# fdcanusb.net
KiCad netlist of a schematic drawn in EAGLE
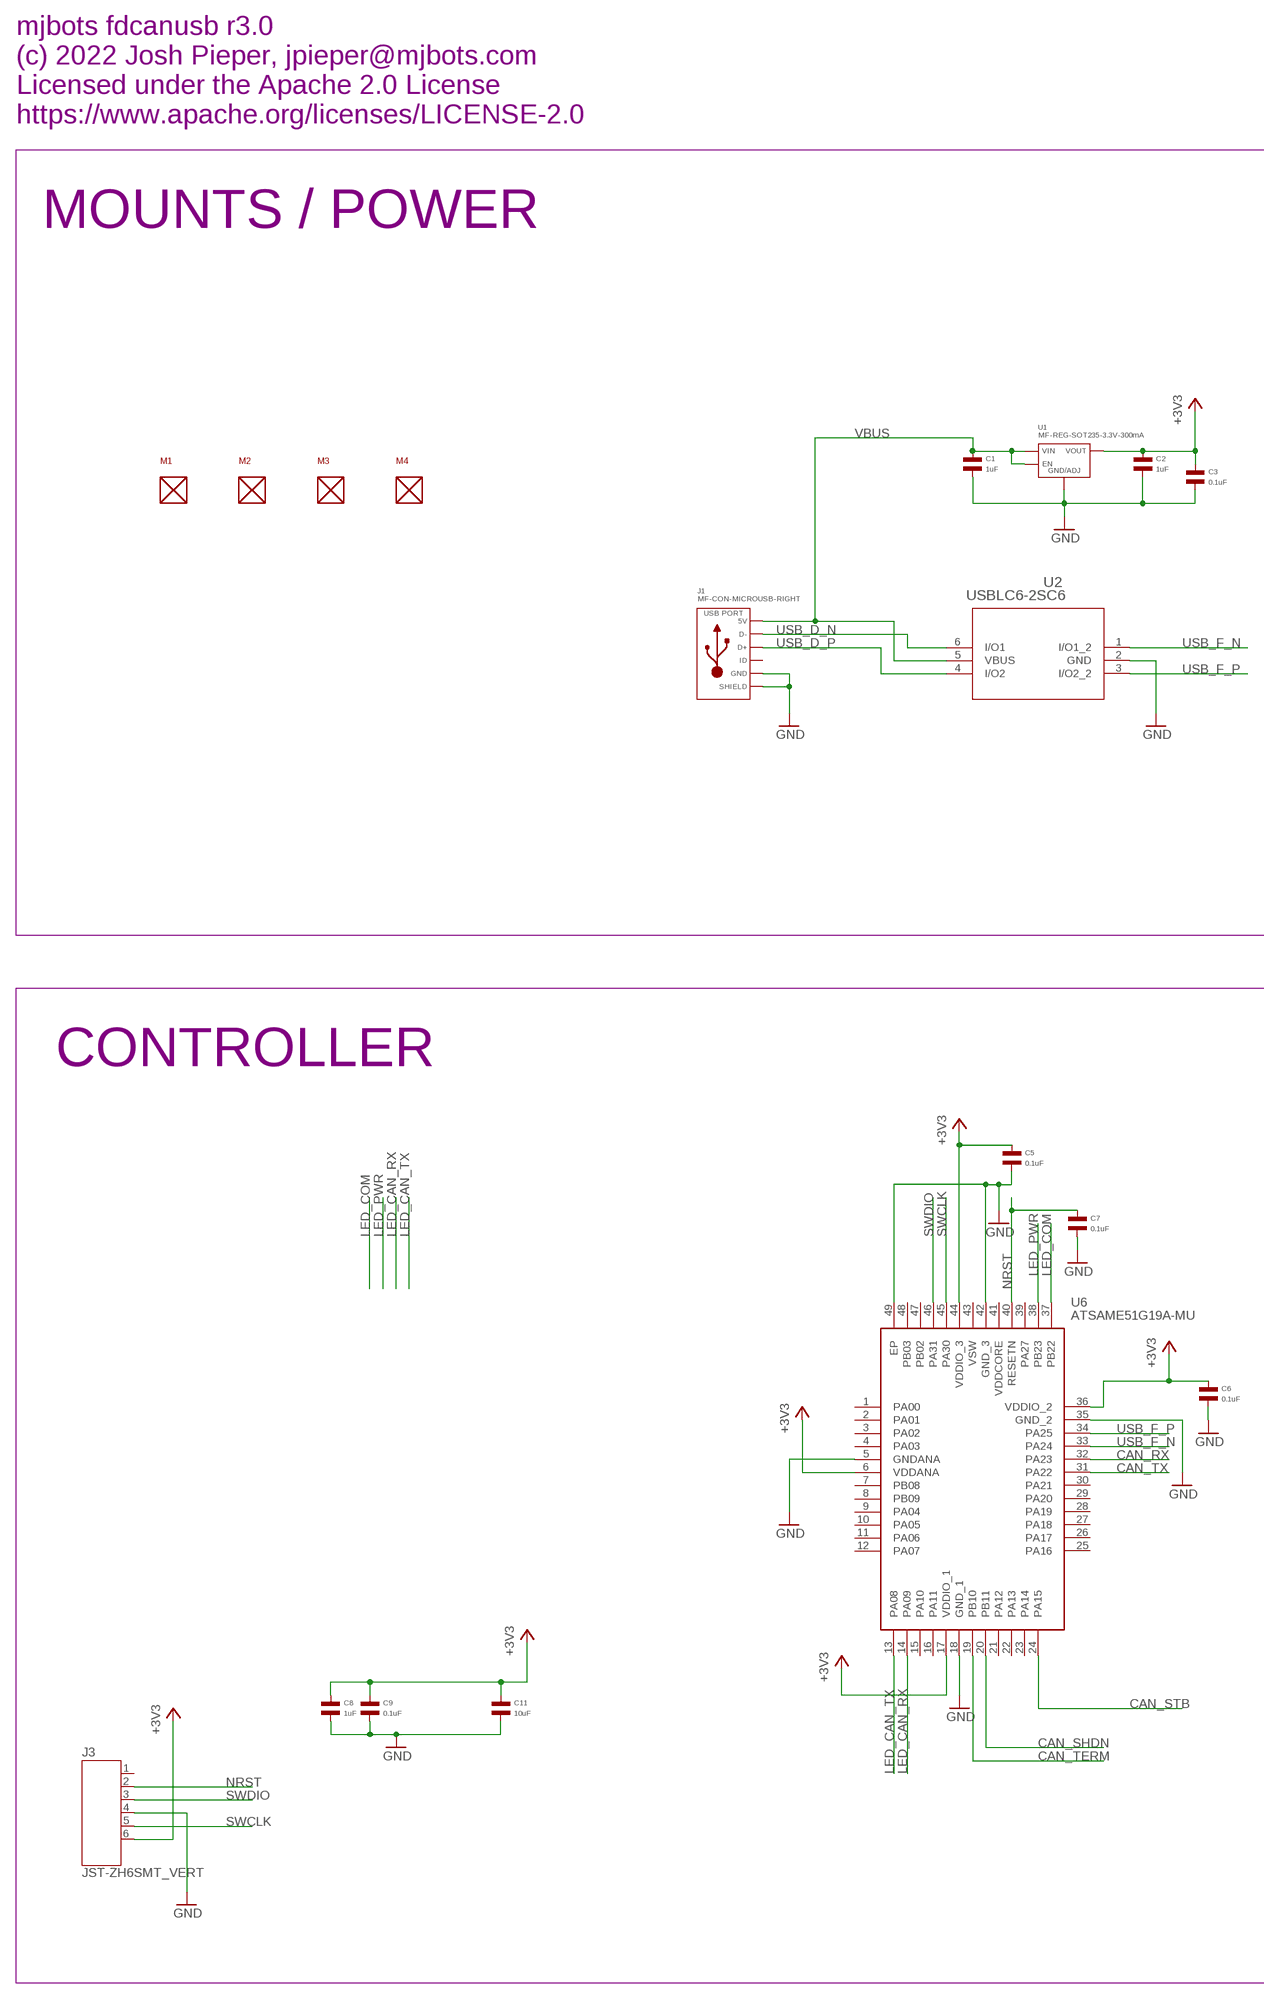
[diagram p0: schematic, sheet 1, part 1 of 2]
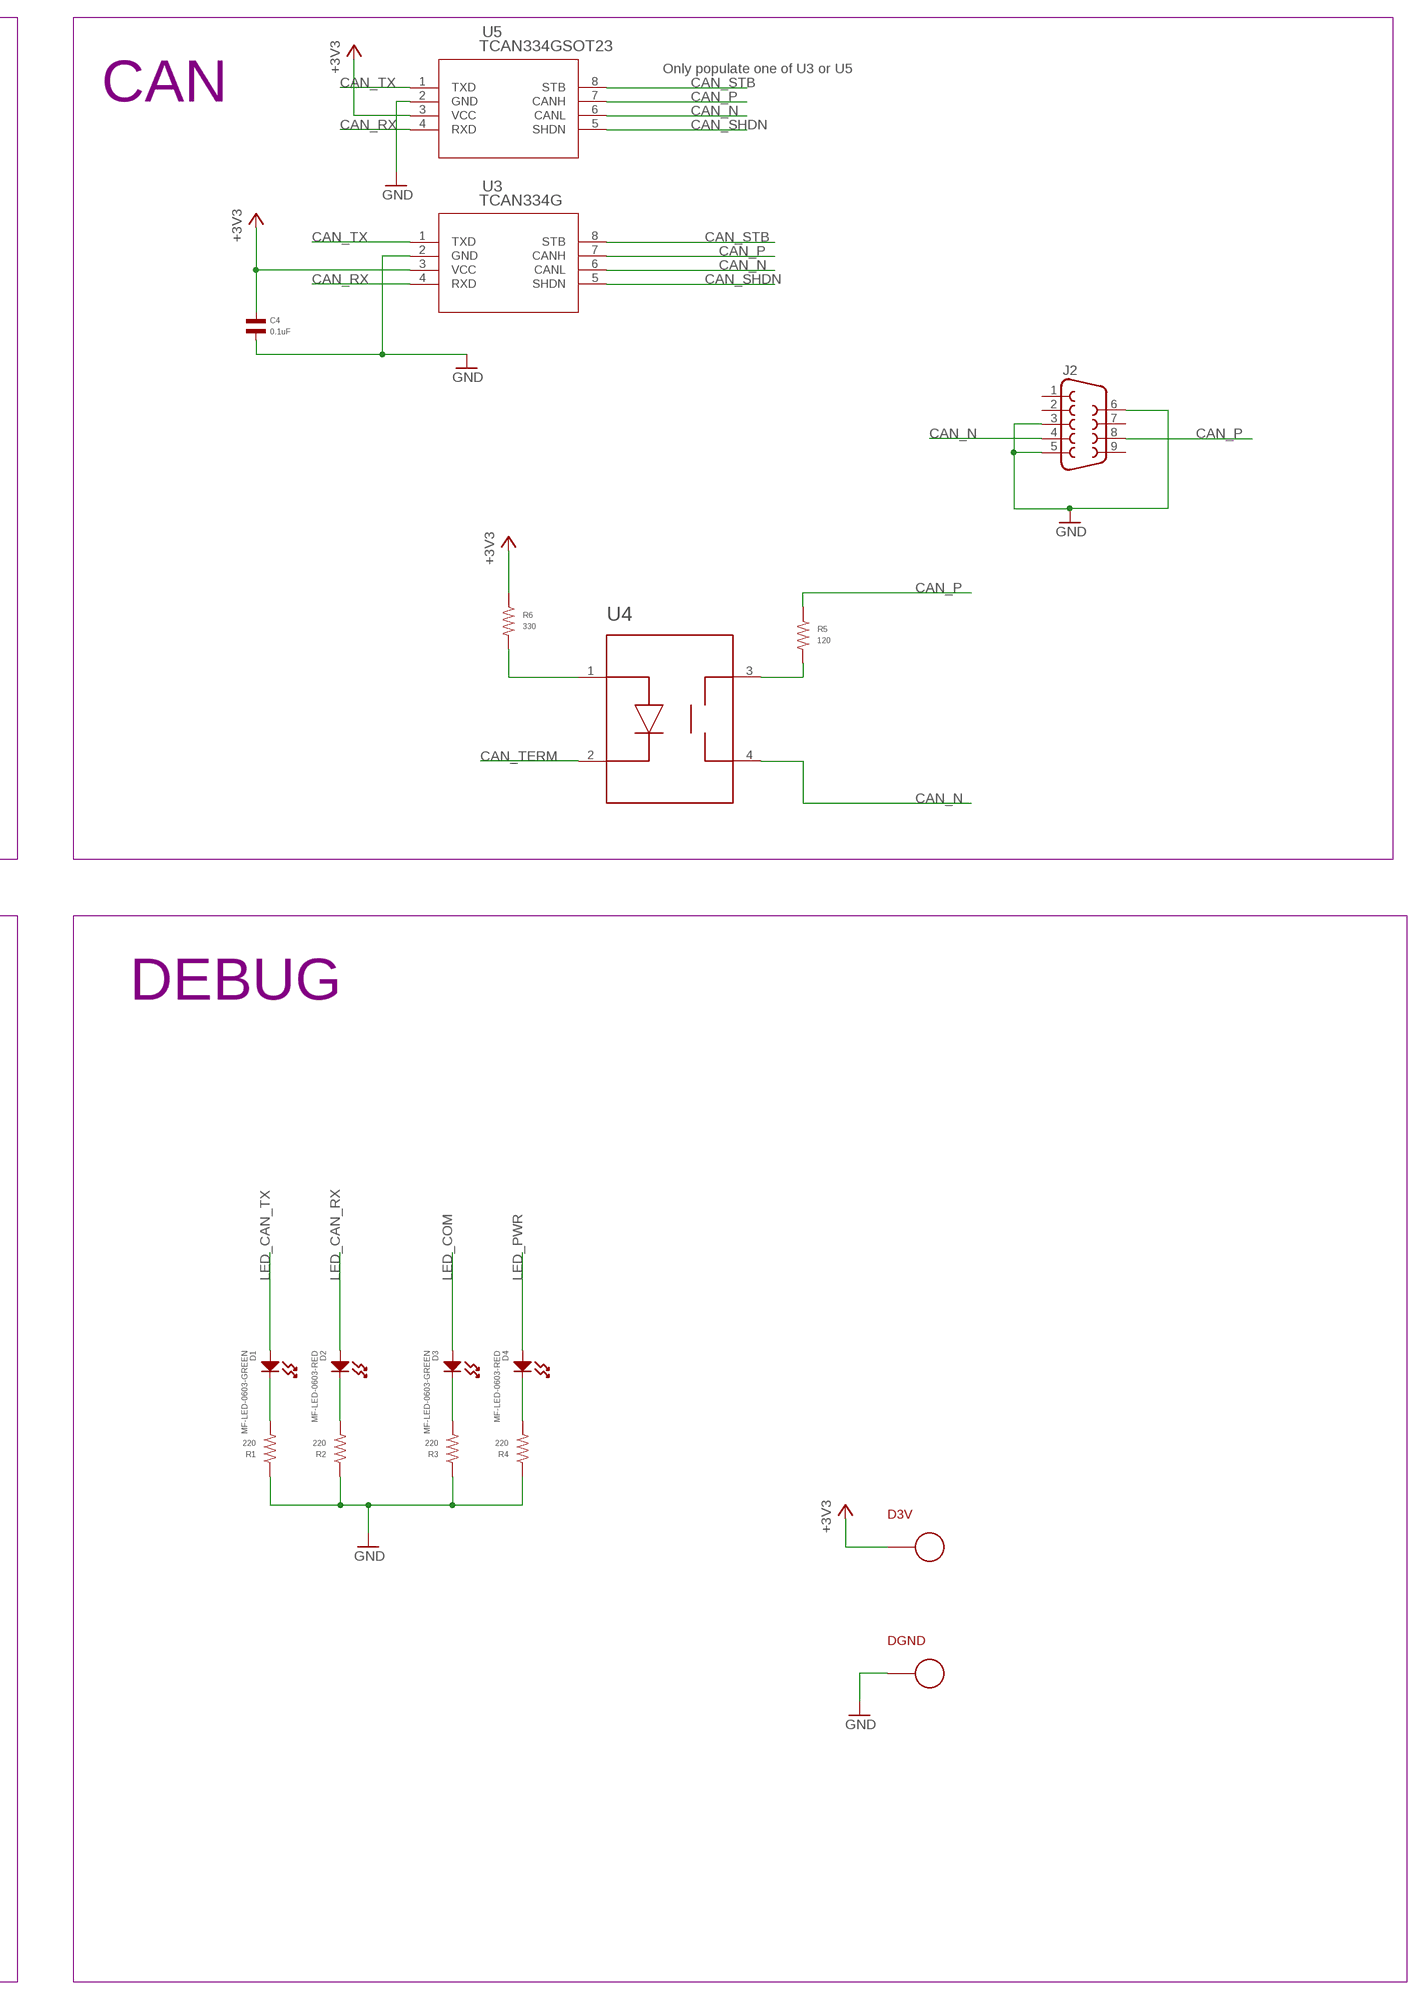
[diagram p1: schematic, sheet 1, part 2 of 2]

(export (version "E")
  (design (tool "Eeschema 10.0.6"))
  (components
    (comp (ref "C1")
      (value "1uF")
      (footprint "eagle-import:C0603")
      (fields (field (name "HOUSEPART") "YES") (field (name "MPN") "MF-CAP-0603-1uF"))
      (libsource (lib "eagle-import") (part "CAPACITOR_NP_0603"))
    )
    (comp (ref "C2")
      (value "1uF")
      (footprint "eagle-import:C0603")
      (fields (field (name "HOUSEPART") "YES") (field (name "MPN") "MF-CAP-0603-1uF"))
      (libsource (lib "eagle-import") (part "CAPACITOR_NP_0603"))
    )
    (comp (ref "C3")
      (value "0.1uF")
      (footprint "eagle-import:C0603")
      (fields (field (name "HOUSEPART") "YES") (field (name "MPN") "MF-CAP-0603-0.1uF"))
      (libsource (lib "eagle-import") (part "CAPACITOR_NP_0603"))
    )
    (comp (ref "C4")
      (value "0.1uF")
      (footprint "eagle-import:C0603")
      (fields (field (name "HOUSEPART") "YES") (field (name "MPN") "MF-CAP-0603-0.1uF"))
      (libsource (lib "eagle-import") (part "CAPACITOR_NP_0603"))
    )
    (comp (ref "C5")
      (value "0.1uF")
      (footprint "eagle-import:C0603")
      (fields (field (name "HOUSEPART") "YES") (field (name "MPN") "MF-CAP-0603-0.1uF"))
      (libsource (lib "eagle-import") (part "CAPACITOR_NP_0603"))
    )
    (comp (ref "C6")
      (value "0.1uF")
      (footprint "eagle-import:C0603")
      (fields (field (name "HOUSEPART") "YES") (field (name "MPN") "MF-CAP-0603-0.1uF"))
      (libsource (lib "eagle-import") (part "CAPACITOR_NP_0603"))
    )
    (comp (ref "C7")
      (value "0.1uF")
      (footprint "eagle-import:C0603")
      (fields (field (name "HOUSEPART") "YES") (field (name "MPN") "MF-CAP-0603-0.1uF"))
      (libsource (lib "eagle-import") (part "CAPACITOR_NP_0603"))
    )
    (comp (ref "C8")
      (value "1uF")
      (footprint "eagle-import:C0603")
      (fields (field (name "HOUSEPART") "YES") (field (name "MPN") "MF-CAP-0603-1uF"))
      (libsource (lib "eagle-import") (part "CAPACITOR_NP_0603"))
    )
    (comp (ref "C9")
      (value "0.1uF")
      (footprint "eagle-import:C0603")
      (fields (field (name "HOUSEPART") "YES") (field (name "MPN") "MF-CAP-0603-0.1uF"))
      (libsource (lib "eagle-import") (part "CAPACITOR_NP_0603"))
    )
    (comp (ref "C11")
      (value "10uF")
      (footprint "eagle-import:C1206")
      (fields (field (name "HOUSEPART") "YES") (field (name "MPN") "MF-CAP-1206-10uF"))
      (libsource (lib "eagle-import") (part "CAPACITOR_NP_1206"))
    )
    (comp (ref "D1")
      (value "MF-LED-0603-GREEN")
      (footprint "eagle-import:LED0603")
      (fields (field (name "HOUSEPART") "YES"))
      (libsource (lib "eagle-import") (part "LED_SINGLE-0603-GREEN"))
    )
    (comp (ref "D2")
      (value "MF-LED-0603-RED")
      (footprint "eagle-import:LED0603")
      (fields (field (name "HOUSEPART") "YES"))
      (libsource (lib "eagle-import") (part "LED_SINGLE-0603-RED"))
    )
    (comp (ref "D3")
      (value "MF-LED-0603-GREEN")
      (footprint "eagle-import:LED0603")
      (fields (field (name "HOUSEPART") "YES"))
      (libsource (lib "eagle-import") (part "LED_SINGLE-0603-GREEN"))
    )
    (comp (ref "D3V")
      (value "PAD24AWG_PAD")
      (footprint "eagle-import:24AWG_PAD")
      (libsource (lib "eagle-import") (part "PAD24AWG_PAD"))
    )
    (comp (ref "D4")
      (value "MF-LED-0603-RED")
      (footprint "eagle-import:LED0603")
      (fields (field (name "HOUSEPART") "YES"))
      (libsource (lib "eagle-import") (part "LED_SINGLE-0603-RED"))
    )
    (comp (ref "DGND")
      (value "PAD24AWG_PAD")
      (footprint "eagle-import:24AWG_PAD")
      (libsource (lib "eagle-import") (part "PAD24AWG_PAD"))
    )
    (comp (ref "J1")
      (value "MF-CON-MICROUSB-RIGHT")
      (footprint "eagle-import:MICROUSB-RIGHT")
      (fields (field (name "HOUSEPART") "YES"))
      (libsource (lib "eagle-import") (part "USB_MICRO_RIGHT"))
    )
    (comp (ref "J2")
      (value "F09")
      (footprint "eagle-import:DB09_PLATED")
      (libsource (lib "eagle-import") (part "F09"))
    )
    (comp (ref "J3")
      (value "JST-ZH6SMT_VERT")
      (footprint "eagle-import:JST_B6B-ZR-SM4-TF(LF)(SN)")
      (fields (field (name "MF") "JST") (field (name "MPN") "B6B-ZR-SM4-TF(LF)(SN)"))
      (libsource (lib "eagle-import") (part "JST-ZH6SMT_VERT"))
    )
    (comp (ref "M1")
      (value "MOUNT")
      (footprint "eagle-import:M2.5MOUNT")
      (libsource (lib "eagle-import") (part "MOUNT"))
    )
    (comp (ref "M2")
      (value "MOUNT")
      (footprint "eagle-import:M2.5MOUNT")
      (libsource (lib "eagle-import") (part "MOUNT"))
    )
    (comp (ref "M3")
      (value "MOUNT")
      (footprint "eagle-import:M2.5MOUNT")
      (libsource (lib "eagle-import") (part "MOUNT"))
    )
    (comp (ref "M4")
      (value "MOUNT")
      (footprint "eagle-import:M2.5MOUNT")
      (libsource (lib "eagle-import") (part "MOUNT"))
    )
    (comp (ref "R1")
      (value "220")
      (footprint "eagle-import:R0603")
      (fields (field (name "HOUSEPART") "YES") (field (name "MPN") "MF-RES-0603-220"))
      (libsource (lib "eagle-import") (part "RESISTOR_0603"))
    )
    (comp (ref "R2")
      (value "220")
      (footprint "eagle-import:R0603")
      (fields (field (name "HOUSEPART") "YES") (field (name "MPN") "MF-RES-0603-220"))
      (libsource (lib "eagle-import") (part "RESISTOR_0603"))
    )
    (comp (ref "R3")
      (value "220")
      (footprint "eagle-import:R0603")
      (fields (field (name "HOUSEPART") "YES") (field (name "MPN") "MF-RES-0603-220"))
      (libsource (lib "eagle-import") (part "RESISTOR_0603"))
    )
    (comp (ref "R4")
      (value "220")
      (footprint "eagle-import:R0603")
      (fields (field (name "HOUSEPART") "YES") (field (name "MPN") "MF-RES-0603-220"))
      (libsource (lib "eagle-import") (part "RESISTOR_0603"))
    )
    (comp (ref "R5")
      (value "120")
      (footprint "eagle-import:R0603")
      (fields (field (name "MF") "YAGEO") (field (name "MPN") "RC0603FR-07120RL"))
      (libsource (lib "eagle-import") (part "RESISTOR_0603"))
    )
    (comp (ref "R6")
      (value "330")
      (footprint "eagle-import:R0603")
      (fields (field (name "HOUSEPART") "YES") (field (name "MPN") "MF-RES-0603-330"))
      (libsource (lib "eagle-import") (part "RESISTOR_0603"))
    )
    (comp (ref "U1")
      (value "MF-REG-SOT235-3.3V-300mA")
      (footprint "eagle-import:SOT-23-5")
      (fields (field (name "HOUSEPART") "YES"))
      (libsource (lib "eagle-import") (part "TLV70233PDBVR"))
    )
    (comp (ref "U2")
      (value "USBLC6-2SC6")
      (footprint "eagle-import:SOT23-6L")
      (fields (field (name "MANUFACTURER_PART_NUMBER") "USBLC62SC6") (field (name "MF") "ST"))
      (libsource (lib "eagle-import") (part "USBLC6-2SC6"))
    )
    (comp (ref "U3")
      (value "TCAN334G")
      (footprint "eagle-import:SOIC8")
      (fields (field (name "MF") "TI") (field (name "MPN") "TCAN330GDR"))
      (libsource (lib "eagle-import") (part "TCAN334G"))
    )
    (comp (ref "U4")
      (value "TLP3317")
      (footprint "eagle-import:TLP3317")
      (fields
        (field (name "MF") "TOSHIBA")
        (field (name "MPN") "TLP3317(TP15,F")
        (field (name "MPN_1") "TLP3317")
      )
      (libsource (lib "eagle-import") (part "TLP3317"))
    )
    (comp (ref "U5")
      (value "TCAN334GSOT23")
      (footprint "eagle-import:SOT23-8")
      (fields (field (name "MF") "TI") (field (name "MPN") "TCAN334GDCNT"))
      (libsource (lib "eagle-import") (part "TCAN334GSOT23"))
    )
    (comp (ref "U6")
      (value "ATSAME51G19A-MU")
      (footprint "eagle-import:QFN50P700X700X90-49N")
      (fields (field (name "MOUSER_PART_NUMBER") "556-ATSAME51G19A-MU"))
      (libsource (lib "eagle-import") (part "ATSAME51G19A-MU"))
    )
  )
  (nets
    (net (code "1") (name "+3V3") (class "Default")
      (node (ref "C11") (pin "P$1") (pinfunction "P$1_P$1") (pintype "passive"))
      (node (ref "C2") (pin "P$1") (pinfunction "P$1_P$1") (pintype "passive"))
      (node (ref "C3") (pin "P$1") (pinfunction "P$1_P$1") (pintype "passive"))
      (node (ref "C4") (pin "P$1") (pinfunction "P$1_P$1") (pintype "passive"))
      (node (ref "C5") (pin "P$1") (pinfunction "P$1_P$1") (pintype "passive"))
      (node (ref "C6") (pin "P$1") (pinfunction "P$1_P$1") (pintype "passive"))
      (node (ref "C8") (pin "P$1") (pinfunction "P$1_P$1") (pintype "passive"))
      (node (ref "C9") (pin "P$1") (pinfunction "P$1_P$1") (pintype "passive"))
      (node (ref "D3V") (pin "P$1") (pinfunction "P$1_P$1") (pintype "bidirectional"))
      (node (ref "J3") (pin "6") (pinfunction "6_6") (pintype "passive"))
      (node (ref "R6") (pin "P$1") (pinfunction "P$1_P$1") (pintype "passive"))
      (node (ref "U1") (pin "P$5") (pinfunction "VOUT_P$5") (pintype "bidirectional"))
      (node (ref "U3") (pin "3") (pinfunction "VCC_3") (pintype "power_in"))
      (node (ref "U5") (pin "3") (pinfunction "VCC_3") (pintype "power_in"))
      (node (ref "U6") (pin "17") (pinfunction "VDDIO_1_17") (pintype "bidirectional"))
      (node (ref "U6") (pin "36") (pinfunction "VDDIO_2_36") (pintype "bidirectional"))
      (node (ref "U6") (pin "44") (pinfunction "VDDIO_3_44") (pintype "bidirectional"))
      (node (ref "U6") (pin "6") (pinfunction "VDDANA_6") (pintype "bidirectional"))
    )
    (net (code "2") (name "/CAN_N") (class "Default")
      (node (ref "J2") (pin "4") (pinfunction "4_4") (pintype "passive"))
      (node (ref "U3") (pin "6") (pinfunction "CANL_6") (pintype "bidirectional"))
      (node (ref "U4") (pin "4") (pinfunction "SW2_4") (pintype "bidirectional"))
      (node (ref "U5") (pin "6") (pinfunction "CANL_6") (pintype "bidirectional"))
    )
    (net (code "3") (name "/CAN_P") (class "Default")
      (node (ref "J2") (pin "8") (pinfunction "8_8") (pintype "passive"))
      (node (ref "R5") (pin "P$1") (pinfunction "P$1_P$1") (pintype "passive"))
      (node (ref "U3") (pin "7") (pinfunction "CANH_7") (pintype "bidirectional"))
      (node (ref "U5") (pin "7") (pinfunction "CANH_7") (pintype "bidirectional"))
    )
    (net (code "4") (name "/CAN_RX") (class "Default")
      (node (ref "U3") (pin "4") (pinfunction "RXD_4") (pintype "output"))
      (node (ref "U5") (pin "4") (pinfunction "RXD_4") (pintype "output"))
      (node (ref "U6") (pin "32") (pinfunction "PA23_32") (pintype "bidirectional"))
    )
    (net (code "5") (name "/CAN_SHDN") (class "Default")
      (node (ref "U3") (pin "5") (pinfunction "SHDN_5") (pintype "input"))
      (node (ref "U5") (pin "5") (pinfunction "SHDN_5") (pintype "input"))
      (node (ref "U6") (pin "20") (pinfunction "PB11_20") (pintype "bidirectional"))
    )
    (net (code "6") (name "/CAN_STB") (class "Default")
      (node (ref "U3") (pin "8") (pinfunction "STB_8") (pintype "input"))
      (node (ref "U5") (pin "8") (pinfunction "STB_8") (pintype "input"))
      (node (ref "U6") (pin "24") (pinfunction "PA15_24") (pintype "bidirectional"))
    )
    (net (code "7") (name "/CAN_TERM") (class "Default")
      (node (ref "U4") (pin "2") (pinfunction "CATHODE_2") (pintype "bidirectional"))
      (node (ref "U6") (pin "19") (pinfunction "PB10_19") (pintype "bidirectional"))
    )
    (net (code "8") (name "/CAN_TX") (class "Default")
      (node (ref "U3") (pin "1") (pinfunction "TXD_1") (pintype "input"))
      (node (ref "U5") (pin "1") (pinfunction "TXD_1") (pintype "input"))
      (node (ref "U6") (pin "31") (pinfunction "PA22_31") (pintype "bidirectional"))
    )
    (net (code "9") (name "/LED_CAN_RX") (class "Default")
      (node (ref "D2") (pin "ANODE") (pinfunction "ANODE_ANODE") (pintype "power_in"))
      (node (ref "U6") (pin "14") (pinfunction "PA09_14") (pintype "bidirectional"))
    )
    (net (code "10") (name "/LED_CAN_TX") (class "Default")
      (node (ref "D1") (pin "ANODE") (pinfunction "ANODE_ANODE") (pintype "power_in"))
      (node (ref "U6") (pin "13") (pinfunction "PA08_13") (pintype "bidirectional"))
    )
    (net (code "11") (name "/LED_COM") (class "Default")
      (node (ref "D3") (pin "ANODE") (pinfunction "ANODE_ANODE") (pintype "power_in"))
      (node (ref "U6") (pin "37") (pinfunction "PB22_37") (pintype "bidirectional"))
    )
    (net (code "12") (name "/LED_PWR") (class "Default")
      (node (ref "D4") (pin "ANODE") (pinfunction "ANODE_ANODE") (pintype "power_in"))
      (node (ref "U6") (pin "38") (pinfunction "PB23_38") (pintype "bidirectional"))
    )
    (net (code "13") (name "/NRST") (class "Default")
      (node (ref "C7") (pin "P$1") (pinfunction "P$1_P$1") (pintype "passive"))
      (node (ref "J3") (pin "2") (pinfunction "2_2") (pintype "passive"))
      (node (ref "U6") (pin "40") (pinfunction "RESETN_40") (pintype "bidirectional"))
    )
    (net (code "14") (name "/SWCLK") (class "Default")
      (node (ref "J3") (pin "5") (pinfunction "5_5") (pintype "passive"))
      (node (ref "U6") (pin "45") (pinfunction "PA30_45") (pintype "bidirectional"))
    )
    (net (code "15") (name "/SWDIO") (class "Default")
      (node (ref "J3") (pin "3") (pinfunction "3_3") (pintype "passive"))
      (node (ref "U6") (pin "46") (pinfunction "PA31_46") (pintype "bidirectional"))
    )
    (net (code "16") (name "/USB_D_N") (class "Default")
      (node (ref "J1") (pin "2") (pinfunction "D-_2") (pintype "bidirectional"))
      (node (ref "U2") (pin "6") (pinfunction "I/O1_6") (pintype "bidirectional"))
    )
    (net (code "17") (name "/USB_D_P") (class "Default")
      (node (ref "J1") (pin "3") (pinfunction "D+_3") (pintype "bidirectional"))
      (node (ref "U2") (pin "4") (pinfunction "I/O2_4") (pintype "bidirectional"))
    )
    (net (code "18") (name "/USB_F_N") (class "Default")
      (node (ref "U2") (pin "1") (pinfunction "I/O1_2_1") (pintype "bidirectional"))
      (node (ref "U6") (pin "33") (pinfunction "PA24_33") (pintype "bidirectional"))
    )
    (net (code "19") (name "/USB_F_P") (class "Default")
      (node (ref "U2") (pin "3") (pinfunction "I/O2_2_3") (pintype "bidirectional"))
      (node (ref "U6") (pin "34") (pinfunction "PA25_34") (pintype "bidirectional"))
    )
    (net (code "20") (name "/VBUS") (class "Default")
      (node (ref "C1") (pin "P$1") (pinfunction "P$1_P$1") (pintype "passive"))
      (node (ref "J1") (pin "1") (pinfunction "5V_1") (pintype "power_in"))
      (node (ref "U1") (pin "P$1") (pinfunction "VIN_P$1") (pintype "bidirectional"))
      (node (ref "U1") (pin "P$3") (pinfunction "EN_P$3") (pintype "bidirectional"))
      (node (ref "U2") (pin "5") (pinfunction "VBUS_5") (pintype "power_in"))
    )
    (net (code "21") (name "GND") (class "Default")
      (node (ref "C1") (pin "P$2") (pinfunction "P$2_P$2") (pintype "passive"))
      (node (ref "C11") (pin "P$2") (pinfunction "P$2_P$2") (pintype "passive"))
      (node (ref "C2") (pin "P$2") (pinfunction "P$2_P$2") (pintype "passive"))
      (node (ref "C3") (pin "P$2") (pinfunction "P$2_P$2") (pintype "passive"))
      (node (ref "C4") (pin "P$2") (pinfunction "P$2_P$2") (pintype "passive"))
      (node (ref "C5") (pin "P$2") (pinfunction "P$2_P$2") (pintype "passive"))
      (node (ref "C6") (pin "P$2") (pinfunction "P$2_P$2") (pintype "passive"))
      (node (ref "C7") (pin "P$2") (pinfunction "P$2_P$2") (pintype "passive"))
      (node (ref "C8") (pin "P$2") (pinfunction "P$2_P$2") (pintype "passive"))
      (node (ref "C9") (pin "P$2") (pinfunction "P$2_P$2") (pintype "passive"))
      (node (ref "DGND") (pin "P$1") (pinfunction "P$1_P$1") (pintype "bidirectional"))
      (node (ref "J1") (pin "5") (pinfunction "GND_5") (pintype "power_in"))
      (node (ref "J1") (pin "S1") (pinfunction "SLD_S1") (pintype "power_in"))
      (node (ref "J1") (pin "S2") (pinfunction "SLD_S2") (pintype "power_in"))
      (node (ref "J1") (pin "S3") (pinfunction "SLD_S3") (pintype "power_in"))
      (node (ref "J1") (pin "S4") (pinfunction "SLD_S4") (pintype "power_in"))
      (node (ref "J1") (pin "S5") (pinfunction "SLD_S5") (pintype "power_in"))
      (node (ref "J1") (pin "S6") (pinfunction "SLD_S6") (pintype "power_in"))
      (node (ref "J2") (pin "3") (pinfunction "3_3") (pintype "passive"))
      (node (ref "J2") (pin "5") (pinfunction "5_5") (pintype "passive"))
      (node (ref "J2") (pin "6") (pinfunction "6_6") (pintype "passive"))
      (node (ref "J3") (pin "4") (pinfunction "4_4") (pintype "passive"))
      (node (ref "R1") (pin "P$1") (pinfunction "P$1_P$1") (pintype "passive"))
      (node (ref "R2") (pin "P$1") (pinfunction "P$1_P$1") (pintype "passive"))
      (node (ref "R3") (pin "P$1") (pinfunction "P$1_P$1") (pintype "passive"))
      (node (ref "R4") (pin "P$1") (pinfunction "P$1_P$1") (pintype "passive"))
      (node (ref "U1") (pin "P$2") (pinfunction "GND/ADJ_P$2") (pintype "bidirectional"))
      (node (ref "U2") (pin "2") (pinfunction "GND_2") (pintype "power_in"))
      (node (ref "U3") (pin "2") (pinfunction "GND_2") (pintype "power_in"))
      (node (ref "U5") (pin "2") (pinfunction "GND_2") (pintype "power_in"))
      (node (ref "U6") (pin "18") (pinfunction "GND_1_18") (pintype "bidirectional"))
      (node (ref "U6") (pin "35") (pinfunction "GND_2_35") (pintype "bidirectional"))
      (node (ref "U6") (pin "42") (pinfunction "GND_3_42") (pintype "bidirectional"))
      (node (ref "U6") (pin "49") (pinfunction "EP_49") (pintype "bidirectional"))
      (node (ref "U6") (pin "5") (pinfunction "GNDANA_5") (pintype "bidirectional"))
    )
    (net (code "22") (name "Net-(D1-PadCATHODE)") (class "Default")
      (node (ref "D1") (pin "CATHODE") (pinfunction "CATHODE_CATHODE") (pintype "power_in"))
      (node (ref "R1") (pin "P$2") (pinfunction "P$2_P$2") (pintype "passive"))
    )
    (net (code "23") (name "Net-(D2-PadCATHODE)") (class "Default")
      (node (ref "D2") (pin "CATHODE") (pinfunction "CATHODE_CATHODE") (pintype "power_in"))
      (node (ref "R2") (pin "P$2") (pinfunction "P$2_P$2") (pintype "passive"))
    )
    (net (code "24") (name "Net-(D3-PadCATHODE)") (class "Default")
      (node (ref "D3") (pin "CATHODE") (pinfunction "CATHODE_CATHODE") (pintype "power_in"))
      (node (ref "R3") (pin "P$2") (pinfunction "P$2_P$2") (pintype "passive"))
    )
    (net (code "25") (name "Net-(D4-PadCATHODE)") (class "Default")
      (node (ref "D4") (pin "CATHODE") (pinfunction "CATHODE_CATHODE") (pintype "power_in"))
      (node (ref "R4") (pin "P$2") (pinfunction "P$2_P$2") (pintype "passive"))
    )
    (net (code "26") (name "Net-(U4-ANODE)") (class "Default")
      (node (ref "R6") (pin "P$2") (pinfunction "P$2_P$2") (pintype "passive"))
      (node (ref "U4") (pin "1") (pinfunction "ANODE_1") (pintype "bidirectional"))
    )
    (net (code "27") (name "Net-(U4-SW1)") (class "Default")
      (node (ref "R5") (pin "P$2") (pinfunction "P$2_P$2") (pintype "passive"))
      (node (ref "U4") (pin "3") (pinfunction "SW1_3") (pintype "bidirectional"))
    )
    (net (code "28") (name "unconnected-(J1-ID-Pad4)") (class "Default")
      (node (ref "J1") (pin "4") (pinfunction "ID_4") (pintype "bidirectional"))
    )
    (net (code "29") (name "unconnected-(J2-Pad1)") (class "Default")
      (node (ref "J2") (pin "1") (pinfunction "1_1") (pintype "passive"))
    )
    (net (code "30") (name "unconnected-(J2-Pad2)") (class "Default")
      (node (ref "J2") (pin "2") (pinfunction "2_2") (pintype "passive"))
    )
    (net (code "31") (name "unconnected-(J2-Pad7)") (class "Default")
      (node (ref "J2") (pin "7") (pinfunction "7_7") (pintype "passive"))
    )
    (net (code "32") (name "unconnected-(J2-Pad9)") (class "Default")
      (node (ref "J2") (pin "9") (pinfunction "9_9") (pintype "passive"))
    )
    (net (code "33") (name "unconnected-(J3-Pad1)") (class "Default")
      (node (ref "J3") (pin "1") (pinfunction "1_1") (pintype "passive"))
    )
    (net (code "34") (name "unconnected-(U6-PA00-Pad1)") (class "Default")
      (node (ref "U6") (pin "1") (pinfunction "PA00_1") (pintype "bidirectional"))
    )
    (net (code "35") (name "unconnected-(U6-PA01-Pad2)") (class "Default")
      (node (ref "U6") (pin "2") (pinfunction "PA01_2") (pintype "bidirectional"))
    )
    (net (code "36") (name "unconnected-(U6-PA02-Pad3)") (class "Default")
      (node (ref "U6") (pin "3") (pinfunction "PA02_3") (pintype "bidirectional"))
    )
    (net (code "37") (name "unconnected-(U6-PA03-Pad4)") (class "Default")
      (node (ref "U6") (pin "4") (pinfunction "PA03_4") (pintype "bidirectional"))
    )
    (net (code "38") (name "unconnected-(U6-PA04-Pad9)") (class "Default")
      (node (ref "U6") (pin "9") (pinfunction "PA04_9") (pintype "bidirectional"))
    )
    (net (code "39") (name "unconnected-(U6-PA05-Pad10)") (class "Default")
      (node (ref "U6") (pin "10") (pinfunction "PA05_10") (pintype "bidirectional"))
    )
    (net (code "40") (name "unconnected-(U6-PA06-Pad11)") (class "Default")
      (node (ref "U6") (pin "11") (pinfunction "PA06_11") (pintype "bidirectional"))
    )
    (net (code "41") (name "unconnected-(U6-PA07-Pad12)") (class "Default")
      (node (ref "U6") (pin "12") (pinfunction "PA07_12") (pintype "bidirectional"))
    )
    (net (code "42") (name "unconnected-(U6-PA10-Pad15)") (class "Default")
      (node (ref "U6") (pin "15") (pinfunction "PA10_15") (pintype "bidirectional"))
    )
    (net (code "43") (name "unconnected-(U6-PA11-Pad16)") (class "Default")
      (node (ref "U6") (pin "16") (pinfunction "PA11_16") (pintype "bidirectional"))
    )
    (net (code "44") (name "unconnected-(U6-PA12-Pad21)") (class "Default")
      (node (ref "U6") (pin "21") (pinfunction "PA12_21") (pintype "bidirectional"))
    )
    (net (code "45") (name "unconnected-(U6-PA13-Pad22)") (class "Default")
      (node (ref "U6") (pin "22") (pinfunction "PA13_22") (pintype "bidirectional"))
    )
    (net (code "46") (name "unconnected-(U6-PA14-Pad23)") (class "Default")
      (node (ref "U6") (pin "23") (pinfunction "PA14_23") (pintype "bidirectional"))
    )
    (net (code "47") (name "unconnected-(U6-PA16-Pad25)") (class "Default")
      (node (ref "U6") (pin "25") (pinfunction "PA16_25") (pintype "bidirectional"))
    )
    (net (code "48") (name "unconnected-(U6-PA17-Pad26)") (class "Default")
      (node (ref "U6") (pin "26") (pinfunction "PA17_26") (pintype "bidirectional"))
    )
    (net (code "49") (name "unconnected-(U6-PA18-Pad27)") (class "Default")
      (node (ref "U6") (pin "27") (pinfunction "PA18_27") (pintype "bidirectional"))
    )
    (net (code "50") (name "unconnected-(U6-PA19-Pad28)") (class "Default")
      (node (ref "U6") (pin "28") (pinfunction "PA19_28") (pintype "bidirectional"))
    )
    (net (code "51") (name "unconnected-(U6-PA20-Pad29)") (class "Default")
      (node (ref "U6") (pin "29") (pinfunction "PA20_29") (pintype "bidirectional"))
    )
    (net (code "52") (name "unconnected-(U6-PA21-Pad30)") (class "Default")
      (node (ref "U6") (pin "30") (pinfunction "PA21_30") (pintype "bidirectional"))
    )
    (net (code "53") (name "unconnected-(U6-PA27-Pad39)") (class "Default")
      (node (ref "U6") (pin "39") (pinfunction "PA27_39") (pintype "bidirectional"))
    )
    (net (code "54") (name "unconnected-(U6-PB02-Pad47)") (class "Default")
      (node (ref "U6") (pin "47") (pinfunction "PB02_47") (pintype "bidirectional"))
    )
    (net (code "55") (name "unconnected-(U6-PB03-Pad48)") (class "Default")
      (node (ref "U6") (pin "48") (pinfunction "PB03_48") (pintype "bidirectional"))
    )
    (net (code "56") (name "unconnected-(U6-PB08-Pad7)") (class "Default")
      (node (ref "U6") (pin "7") (pinfunction "PB08_7") (pintype "bidirectional"))
    )
    (net (code "57") (name "unconnected-(U6-PB09-Pad8)") (class "Default")
      (node (ref "U6") (pin "8") (pinfunction "PB09_8") (pintype "bidirectional"))
    )
    (net (code "58") (name "unconnected-(U6-VDDCORE-Pad41)") (class "Default")
      (node (ref "U6") (pin "41") (pinfunction "VDDCORE_41") (pintype "bidirectional"))
    )
    (net (code "59") (name "unconnected-(U6-VSW-Pad43)") (class "Default")
      (node (ref "U6") (pin "43") (pinfunction "VSW_43") (pintype "bidirectional"))
    )
  )
)
